# FPGA_Bank_IO.net
KiCad netlist of a schematic drawn in Altium Designer
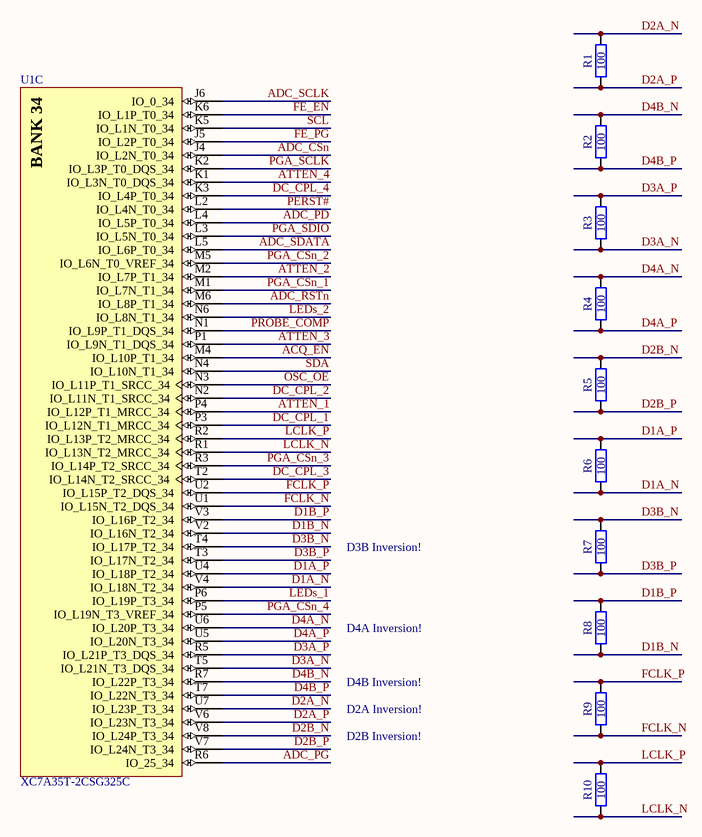
[diagram p0: FPGA_Bank_IO.SchDoc]

(export (version "E")
  (design (tool "Eeschema 10.0.6"))
  (components
    (comp (ref "R1")
      (value "100")
      (footprint "GEN_R_0201")
      (fields (field (name "TOLERANCE") "1%"))
      (libsource (lib "DSO") (part "RES 100 OHM 1% 1/20W 0201"))
    )
    (comp (ref "R2")
      (value "100")
      (footprint "GEN_R_0201")
      (fields (field (name "TOLERANCE") "1%"))
      (libsource (lib "DSO") (part "RES 100 OHM 1% 1/20W 0201"))
    )
    (comp (ref "R3")
      (value "100")
      (footprint "GEN_R_0201")
      (fields (field (name "TOLERANCE") "1%"))
      (libsource (lib "DSO") (part "RES 100 OHM 1% 1/20W 0201"))
    )
    (comp (ref "R4")
      (value "100")
      (footprint "GEN_R_0201")
      (fields (field (name "TOLERANCE") "1%"))
      (libsource (lib "DSO") (part "RES 100 OHM 1% 1/20W 0201"))
    )
    (comp (ref "R5")
      (value "100")
      (footprint "GEN_R_0201")
      (fields (field (name "TOLERANCE") "1%"))
      (libsource (lib "DSO") (part "RES 100 OHM 1% 1/20W 0201"))
    )
    (comp (ref "R6")
      (value "100")
      (footprint "GEN_R_0201")
      (fields (field (name "TOLERANCE") "1%"))
      (libsource (lib "DSO") (part "RES 100 OHM 1% 1/20W 0201"))
    )
    (comp (ref "R7")
      (value "100")
      (footprint "GEN_R_0201")
      (fields (field (name "TOLERANCE") "1%"))
      (libsource (lib "DSO") (part "RES 100 OHM 1% 1/20W 0201"))
    )
    (comp (ref "R8")
      (value "100")
      (footprint "GEN_R_0201")
      (fields (field (name "TOLERANCE") "1%"))
      (libsource (lib "DSO") (part "RES 100 OHM 1% 1/20W 0201"))
    )
    (comp (ref "R9")
      (value "100")
      (footprint "GEN_R_0201")
      (fields (field (name "TOLERANCE") "1%"))
      (libsource (lib "DSO") (part "RES 100 OHM 1% 1/20W 0201"))
    )
    (comp (ref "R10")
      (value "100")
      (footprint "GEN_R_0201")
      (fields (field (name "TOLERANCE") "1%"))
      (libsource (lib "DSO") (part "RES 100 OHM 1% 1/20W 0201"))
    )
    (comp (ref "U1")
      (value "XC7A35T-2CSG325C")
      (footprint "CSG325")
      (description "Artix-7 FPGA, 150 User I/Os, 4 GTP, 324-Ball BGA, Speed Grade 2, Commercial Grade, Pb-Free")
      (fields (field (name "MANUFACTURER") "Xilinx"))
      (libsource (lib "Xilinx Artix-7") (part "XC7A35T-2CSG325C"))
    )
  )
  (nets
    (net (code "1") (name "/ACQ_EN") (class "Default")
      (node (ref "U1") (pin "M4") (pinfunction "IO_L10P_T1_34_M4") (pintype "bidirectional"))
    )
    (net (code "2") (name "/ADC_CSn") (class "Default")
      (node (ref "U1") (pin "J4") (pinfunction "IO_L2N_T0_34_J4") (pintype "bidirectional"))
    )
    (net (code "3") (name "/ADC_PD") (class "Default")
      (node (ref "U1") (pin "L4") (pinfunction "IO_L5P_T0_34_L4") (pintype "bidirectional"))
    )
    (net (code "4") (name "/ADC_PG") (class "Default")
      (node (ref "U1") (pin "R6") (pinfunction "IO_25_34_R6") (pintype "bidirectional"))
    )
    (net (code "5") (name "/ADC_RSTn") (class "Default")
      (node (ref "U1") (pin "M6") (pinfunction "IO_L8P_T1_34_M6") (pintype "bidirectional"))
    )
    (net (code "6") (name "/ADC_SCLK") (class "Default")
      (node (ref "U1") (pin "J6") (pinfunction "IO_0_34_J6") (pintype "bidirectional"))
    )
    (net (code "7") (name "/ADC_SDATA") (class "Default")
      (node (ref "U1") (pin "L5") (pinfunction "IO_L6P_T0_34_L5") (pintype "bidirectional"))
    )
    (net (code "8") (name "/ATTEN_1") (class "Default")
      (node (ref "U1") (pin "P4") (pinfunction "IO_L12P_T1_MRCC_34_P4") (pintype "bidirectional"))
    )
    (net (code "9") (name "/ATTEN_2") (class "Default")
      (node (ref "U1") (pin "M2") (pinfunction "IO_L7P_T1_34_M2") (pintype "bidirectional"))
    )
    (net (code "10") (name "/ATTEN_3") (class "Default")
      (node (ref "U1") (pin "P1") (pinfunction "IO_L9N_T1_DQS_34_P1") (pintype "bidirectional"))
    )
    (net (code "11") (name "/ATTEN_4") (class "Default")
      (node (ref "U1") (pin "K1") (pinfunction "IO_L3N_T0_DQS_34_K1") (pintype "bidirectional"))
    )
    (net (code "12") (name "/D1A_N") (class "Default")
      (node (ref "R6") (pin "1") (pinfunction "1_1") (pintype "passive"))
      (node (ref "U1") (pin "V4") (pinfunction "IO_L18N_T2_34_V4") (pintype "bidirectional"))
    )
    (net (code "13") (name "/D1A_P") (class "Default")
      (node (ref "R6") (pin "2") (pinfunction "2_2") (pintype "passive"))
      (node (ref "U1") (pin "U4") (pinfunction "IO_L18P_T2_34_U4") (pintype "bidirectional"))
    )
    (net (code "14") (name "/D1B_N") (class "Default")
      (node (ref "R8") (pin "1") (pinfunction "1_1") (pintype "passive"))
      (node (ref "U1") (pin "V2") (pinfunction "IO_L16N_T2_34_V2") (pintype "bidirectional"))
    )
    (net (code "15") (name "/D1B_P") (class "Default")
      (node (ref "R8") (pin "2") (pinfunction "2_2") (pintype "passive"))
      (node (ref "U1") (pin "V3") (pinfunction "IO_L16P_T2_34_V3") (pintype "bidirectional"))
    )
    (net (code "16") (name "/D2A_N") (class "Default")
      (node (ref "R1") (pin "2") (pinfunction "2_2") (pintype "passive"))
      (node (ref "U1") (pin "U7") (pinfunction "IO_L23P_T3_34_U7") (pintype "bidirectional"))
    )
    (net (code "17") (name "/D2A_P") (class "Default")
      (node (ref "R1") (pin "1") (pinfunction "1_1") (pintype "passive"))
      (node (ref "U1") (pin "V6") (pinfunction "IO_L23N_T3_34_V6") (pintype "bidirectional"))
    )
    (net (code "18") (name "/D2B_N") (class "Default")
      (node (ref "R5") (pin "2") (pinfunction "2_2") (pintype "passive"))
      (node (ref "U1") (pin "V8") (pinfunction "IO_L24P_T3_34_V8") (pintype "bidirectional"))
    )
    (net (code "19") (name "/D2B_P") (class "Default")
      (node (ref "R5") (pin "1") (pinfunction "1_1") (pintype "passive"))
      (node (ref "U1") (pin "V7") (pinfunction "IO_L24N_T3_34_V7") (pintype "bidirectional"))
    )
    (net (code "20") (name "/D3A_N") (class "Default")
      (node (ref "R3") (pin "1") (pinfunction "1_1") (pintype "passive"))
      (node (ref "U1") (pin "T5") (pinfunction "IO_L21N_T3_DQS_34_T5") (pintype "bidirectional"))
    )
    (net (code "21") (name "/D3A_P") (class "Default")
      (node (ref "R3") (pin "2") (pinfunction "2_2") (pintype "passive"))
      (node (ref "U1") (pin "R5") (pinfunction "IO_L21P_T3_DQS_34_R5") (pintype "bidirectional"))
    )
    (net (code "22") (name "/D3B_N") (class "Default")
      (node (ref "R7") (pin "2") (pinfunction "2_2") (pintype "passive"))
      (node (ref "U1") (pin "T4") (pinfunction "IO_L17P_T2_34_T4") (pintype "bidirectional"))
    )
    (net (code "23") (name "/D3B_P") (class "Default")
      (node (ref "R7") (pin "1") (pinfunction "1_1") (pintype "passive"))
      (node (ref "U1") (pin "T3") (pinfunction "IO_L17N_T2_34_T3") (pintype "bidirectional"))
    )
    (net (code "24") (name "/D4A_N") (class "Default")
      (node (ref "R4") (pin "2") (pinfunction "2_2") (pintype "passive"))
      (node (ref "U1") (pin "U6") (pinfunction "IO_L20P_T3_34_U6") (pintype "bidirectional"))
    )
    (net (code "25") (name "/D4A_P") (class "Default")
      (node (ref "R4") (pin "1") (pinfunction "1_1") (pintype "passive"))
      (node (ref "U1") (pin "U5") (pinfunction "IO_L20N_T3_34_U5") (pintype "bidirectional"))
    )
    (net (code "26") (name "/D4B_N") (class "Default")
      (node (ref "R2") (pin "2") (pinfunction "2_2") (pintype "passive"))
      (node (ref "U1") (pin "R7") (pinfunction "IO_L22P_T3_34_R7") (pintype "bidirectional"))
    )
    (net (code "27") (name "/D4B_P") (class "Default")
      (node (ref "R2") (pin "1") (pinfunction "1_1") (pintype "passive"))
      (node (ref "U1") (pin "T7") (pinfunction "IO_L22N_T3_34_T7") (pintype "bidirectional"))
    )
    (net (code "28") (name "/DC_CPL_1") (class "Default")
      (node (ref "U1") (pin "P3") (pinfunction "IO_L12N_T1_MRCC_34_P3") (pintype "bidirectional"))
    )
    (net (code "29") (name "/DC_CPL_2") (class "Default")
      (node (ref "U1") (pin "N2") (pinfunction "IO_L11N_T1_SRCC_34_N2") (pintype "bidirectional"))
    )
    (net (code "30") (name "/DC_CPL_3") (class "Default")
      (node (ref "U1") (pin "T2") (pinfunction "IO_L14N_T2_SRCC_34_T2") (pintype "bidirectional"))
    )
    (net (code "31") (name "/DC_CPL_4") (class "Default")
      (node (ref "U1") (pin "K3") (pinfunction "IO_L4P_T0_34_K3") (pintype "bidirectional"))
    )
    (net (code "32") (name "/FCLK_N") (class "Default")
      (node (ref "R9") (pin "1") (pinfunction "1_1") (pintype "passive"))
      (node (ref "U1") (pin "U1") (pinfunction "IO_L15N_T2_DQS_34_U1") (pintype "bidirectional"))
    )
    (net (code "33") (name "/FCLK_P") (class "Default")
      (node (ref "R9") (pin "2") (pinfunction "2_2") (pintype "passive"))
      (node (ref "U1") (pin "U2") (pinfunction "IO_L15P_T2_DQS_34_U2") (pintype "bidirectional"))
    )
    (net (code "34") (name "/FE_EN") (class "Default")
      (node (ref "U1") (pin "K6") (pinfunction "IO_L1P_T0_34_K6") (pintype "bidirectional"))
    )
    (net (code "35") (name "/FE_PG") (class "Default")
      (node (ref "U1") (pin "J5") (pinfunction "IO_L2P_T0_34_J5") (pintype "bidirectional"))
    )
    (net (code "36") (name "/LCLK_N") (class "Default")
      (node (ref "R10") (pin "1") (pinfunction "1_1") (pintype "passive"))
      (node (ref "U1") (pin "R1") (pinfunction "IO_L13N_T2_MRCC_34_R1") (pintype "bidirectional"))
    )
    (net (code "37") (name "/LCLK_P") (class "Default")
      (node (ref "R10") (pin "2") (pinfunction "2_2") (pintype "passive"))
      (node (ref "U1") (pin "R2") (pinfunction "IO_L13P_T2_MRCC_34_R2") (pintype "bidirectional"))
    )
    (net (code "38") (name "/LEDs_1") (class "Default")
      (node (ref "U1") (pin "P6") (pinfunction "IO_L19P_T3_34_P6") (pintype "bidirectional"))
    )
    (net (code "39") (name "/LEDs_2") (class "Default")
      (node (ref "U1") (pin "N6") (pinfunction "IO_L8N_T1_34_N6") (pintype "bidirectional"))
    )
    (net (code "40") (name "/OSC_OE") (class "Default")
      (node (ref "U1") (pin "N3") (pinfunction "IO_L11P_T1_SRCC_34_N3") (pintype "bidirectional"))
    )
    (net (code "41") (name "/PERST#") (class "Default")
      (node (ref "U1") (pin "L2") (pinfunction "IO_L4N_T0_34_L2") (pintype "bidirectional"))
    )
    (net (code "42") (name "/PGA_CSn_1") (class "Default")
      (node (ref "U1") (pin "M1") (pinfunction "IO_L7N_T1_34_M1") (pintype "bidirectional"))
    )
    (net (code "43") (name "/PGA_CSn_2") (class "Default")
      (node (ref "U1") (pin "M5") (pinfunction "IO_L6N_T0_VREF_34_M5") (pintype "bidirectional"))
    )
    (net (code "44") (name "/PGA_CSn_3") (class "Default")
      (node (ref "U1") (pin "R3") (pinfunction "IO_L14P_T2_SRCC_34_R3") (pintype "bidirectional"))
    )
    (net (code "45") (name "/PGA_CSn_4") (class "Default")
      (node (ref "U1") (pin "P5") (pinfunction "IO_L19N_T3_VREF_34_P5") (pintype "bidirectional"))
    )
    (net (code "46") (name "/PGA_SCLK") (class "Default")
      (node (ref "U1") (pin "K2") (pinfunction "IO_L3P_T0_DQS_34_K2") (pintype "bidirectional"))
    )
    (net (code "47") (name "/PGA_SDIO") (class "Default")
      (node (ref "U1") (pin "L3") (pinfunction "IO_L5N_T0_34_L3") (pintype "bidirectional"))
    )
    (net (code "48") (name "/PROBE_COMP") (class "Default")
      (node (ref "U1") (pin "N1") (pinfunction "IO_L9P_T1_DQS_34_N1") (pintype "bidirectional"))
    )
    (net (code "49") (name "/SCL") (class "Default")
      (node (ref "U1") (pin "K5") (pinfunction "IO_L1N_T0_34_K5") (pintype "bidirectional"))
    )
    (net (code "50") (name "/SDA") (class "Default")
      (node (ref "U1") (pin "N4") (pinfunction "IO_L10N_T1_34_N4") (pintype "bidirectional"))
    )
  )
)
